# mipi.net
KiCad netlist of a schematic drawn in EasyEDA Pro
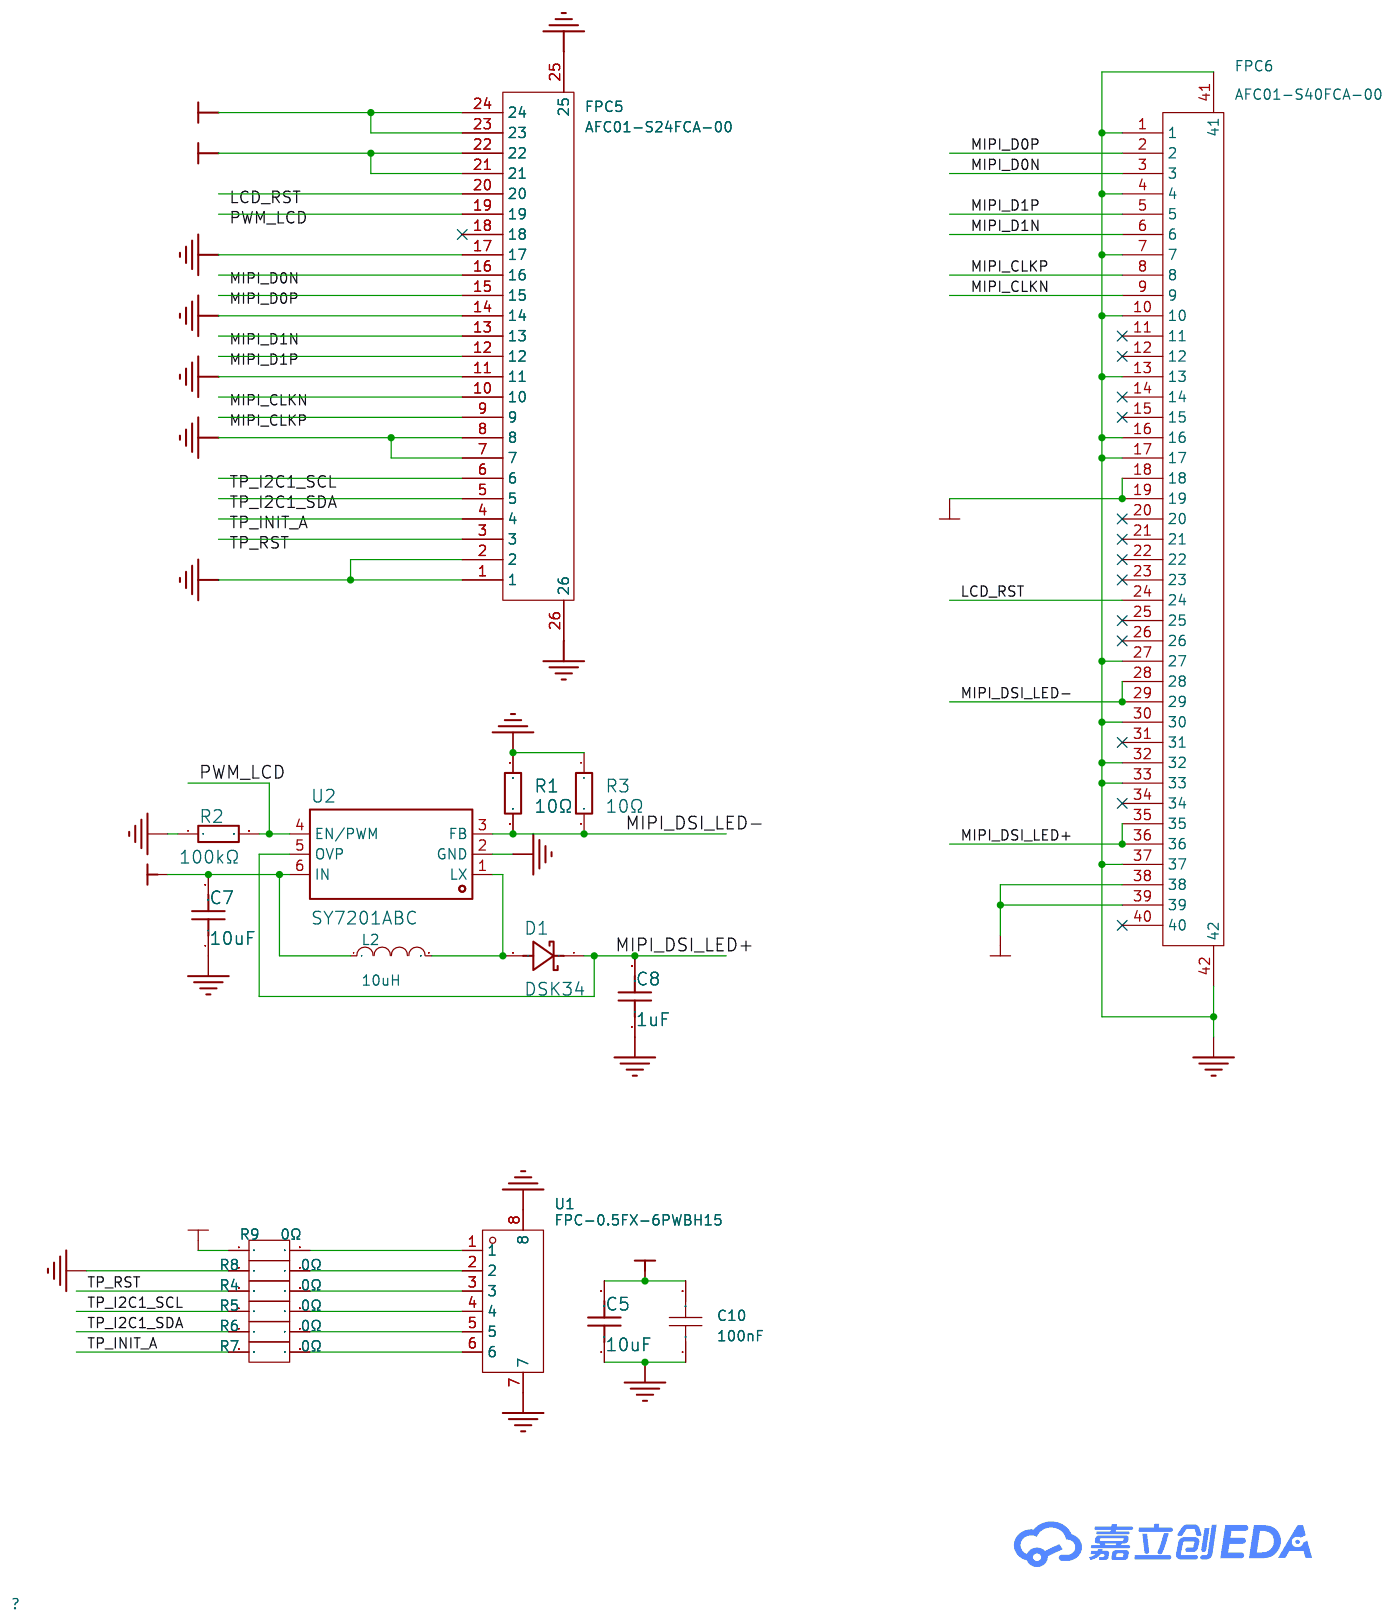
[diagram p0: schematic sheet]

(export (version "E")
  (design (tool "Eeschema 10.0.6"))
  (components
    (comp (ref "C5")
      (value "10uF")
      (fields
        (field (name "Manufacturer Part") "CL21A106KAYNNNE")
        (field (name "Manufacturer") "SAMSUNG(三星)")
      )
      (libsource (lib "easyedapro") (part "CapAcitance"))
    )
    (comp (ref "C7")
      (value "10uF")
      (fields
        (field (name "Manufacturer Part") "CL21A106KAYNNNE")
        (field (name "Manufacturer") "SAMSUNG(三星)")
      )
      (libsource (lib "easyedapro") (part "CapAcitance"))
    )
    (comp (ref "C8")
      (value "1uF")
      (description "容值:1uF;精度:±10%;额定电压:50V;温度系数:X7R;")
      (fields
        (field (name "Manufacturer Part") "CL21B105KBFNNNE")
        (field (name "Manufacturer") "SAMSUNG(三星)")
      )
      (libsource (lib "easyedapro") (part "CapAcitance"))
    )
    (comp (ref "C10")
      (value "100nF")
      (footprint "easyedapro:CAP-SMD_L2.0-W1.25")
      (description "容值:100nF;精度:±10%;额定电压:50V;温度系数:X7R;")
      (fields
        (field (name "Manufacturer Part") "C0805S104K5RACAUTO")
        (field (name "Manufacturer") "KEMET(基美)")
      )
      (libsource (lib "easyedapro") (part "FCC0805B104K500DT"))
    )
    (comp (ref "D1")
      (value "DSK34")
      (footprint "easyedapro:SOD-123_L2.8-W1.8-LS3.7-RD")
      (fields (field (name "Manufacturer") "FUXINSEMI(富芯森美)"))
      (libsource (lib "easyedapro") (part "DSK34_C908230"))
    )
    (comp (ref "FPC5")
      (value "AFC01-S24FCA-00")
      (footprint "easyedapro:FPC-SMD_24P-P0.50_AFC01-S24FCA-00")
      (description "锁定特性:翻盖式;触点类型:下接;触点数量:24P;间距:0.5mm;安装类型:卧贴;")
      (fields (field (name "Manufacturer") "JS(钜硕电子)"))
      (libsource (lib "easyedapro") (part "AFC01-S24FCA-00"))
    )
    (comp (ref "FPC6")
      (value "AFC01-S40FCA-00")
      (footprint "easyedapro:FPC-SMD_AFC01-S40FCA-00")
      (description "锁定特性:翻盖式;触点类型:下接;触点数量:40P;间距:0.5mm;安装方式:卧贴;工作温度:-45°C~+85°C;")
      (fields (field (name "Manufacturer") "JS(钜硕电子)"))
      (libsource (lib "easyedapro") (part "AFC01-S40FCA-00"))
    )
    (comp (ref "L2")
      (value "10uH")
      (footprint "easyedapro:IND-SMD_L7.3-W6.8")
      (description "电感值:10uH;精度:±20%;额定电流:4.5A;饱和电流(Isat):5.5A;类型:一体成型电感;")
      (fields (field (name "Manufacturer Part") "FXL0630-100-M") (field (name "Manufacturer") "cjiang(长江微电)"))
      (libsource (lib "easyedapro") (part "FXL0630-100-M"))
    )
    (comp (ref "R1")
      (value "10Ω")
      (fields
        (field (name "Manufacturer Part") "0603WAF360KT5E")
        (field (name "Manufacturer") "UNI-ROYAL(厚声)")
      )
      (libsource (lib "easyedapro") (part "电阻"))
    )
    (comp (ref "R2")
      (value "100kΩ")
      (fields
        (field (name "Manufacturer Part") "0805W8F1003T5E")
        (field (name "Manufacturer") "UNI-ROYAL(厚声)")
      )
      (libsource (lib "easyedapro") (part "电阻"))
    )
    (comp (ref "R3")
      (value "10Ω")
      (fields
        (field (name "Manufacturer Part") "0603WAF360KT5E")
        (field (name "Manufacturer") "UNI-ROYAL(厚声)")
      )
      (libsource (lib "easyedapro") (part "电阻"))
    )
    (comp (ref "R4")
      (value "0Ω")
      (footprint "easyedapro:R0805")
      (description "电阻类型:合金电阻;阻值:0Ω;精度:±1%;功率:500mW;温度系数:±50ppm/°C;安装方式:贴片;")
      (fields (field (name "Manufacturer Part") "RE0805FAR000") (field (name "Manufacturer") "JIERR(捷而瑞)"))
      (libsource (lib "easyedapro") (part "RE0805FAR000"))
    )
    (comp (ref "R5")
      (value "0Ω")
      (footprint "easyedapro:R0805")
      (description "电阻类型:合金电阻;阻值:0Ω;精度:±1%;功率:500mW;温度系数:±50ppm/°C;安装方式:贴片;")
      (fields (field (name "Manufacturer Part") "RE0805FAR000") (field (name "Manufacturer") "JIERR(捷而瑞)"))
      (libsource (lib "easyedapro") (part "RE0805FAR000"))
    )
    (comp (ref "R6")
      (value "0Ω")
      (footprint "easyedapro:R0805")
      (description "电阻类型:合金电阻;阻值:0Ω;精度:±1%;功率:500mW;温度系数:±50ppm/°C;安装方式:贴片;")
      (fields (field (name "Manufacturer Part") "RE0805FAR000") (field (name "Manufacturer") "JIERR(捷而瑞)"))
      (libsource (lib "easyedapro") (part "RE0805FAR000"))
    )
    (comp (ref "R7")
      (value "0Ω")
      (footprint "easyedapro:R0805")
      (description "电阻类型:合金电阻;阻值:0Ω;精度:±1%;功率:500mW;温度系数:±50ppm/°C;安装方式:贴片;")
      (fields (field (name "Manufacturer Part") "RE0805FAR000") (field (name "Manufacturer") "JIERR(捷而瑞)"))
      (libsource (lib "easyedapro") (part "RE0805FAR000"))
    )
    (comp (ref "R8")
      (value "0Ω")
      (footprint "easyedapro:R0805")
      (description "电阻类型:合金电阻;阻值:0Ω;精度:±1%;功率:500mW;温度系数:±50ppm/°C;安装方式:贴片;")
      (fields (field (name "Manufacturer Part") "RE0805FAR000") (field (name "Manufacturer") "JIERR(捷而瑞)"))
      (libsource (lib "easyedapro") (part "RE0805FAR000"))
    )
    (comp (ref "R9")
      (value "0Ω")
      (footprint "easyedapro:R0805")
      (description "电阻类型:合金电阻;阻值:0Ω;精度:±1%;功率:500mW;温度系数:±50ppm/°C;安装方式:贴片;")
      (fields (field (name "Manufacturer Part") "RE0805FAR000") (field (name "Manufacturer") "JIERR(捷而瑞)"))
      (libsource (lib "easyedapro") (part "RE0805FAR000"))
    )
    (comp (ref "U1")
      (value "FPC-0.5FX-6PWBH15")
      (footprint "easyedapro:FPC-SMD_XUNPU_FPC-0.5FX-6PWBH15")
      (fields (field (name "Manufacturer") "XUNPU(讯普)"))
      (libsource (lib "easyedapro") (part "FPC-0.5FX-6PWBH15"))
    )
    (comp (ref "U2")
      (value "SY7201ABC")
      (fields (field (name "Manufacturer") "Silergy(矽力杰)"))
      (libsource (lib "easyedapro") (part "SY7201ABC"))
    )
  )
  (nets
    (net (code "1") (name "/LCD_RST") (class "Default")
      (node (ref "FPC5") (pin "20") (pinfunction "20_20") (pintype "unspecified"))
      (node (ref "FPC6") (pin "24") (pinfunction "24_24") (pintype "unspecified"))
    )
    (net (code "2") (name "/MIPI_CLKN") (class "Default")
      (node (ref "FPC5") (pin "10") (pinfunction "10_10") (pintype "unspecified"))
      (node (ref "FPC6") (pin "9") (pinfunction "9_9") (pintype "unspecified"))
    )
    (net (code "3") (name "/MIPI_CLKP") (class "Default")
      (node (ref "FPC5") (pin "9") (pinfunction "9_9") (pintype "unspecified"))
      (node (ref "FPC6") (pin "8") (pinfunction "8_8") (pintype "unspecified"))
    )
    (net (code "4") (name "/MIPI_D0N") (class "Default")
      (node (ref "FPC5") (pin "16") (pinfunction "16_16") (pintype "unspecified"))
      (node (ref "FPC6") (pin "3") (pinfunction "3_3") (pintype "unspecified"))
    )
    (net (code "5") (name "/MIPI_D0P") (class "Default")
      (node (ref "FPC5") (pin "15") (pinfunction "15_15") (pintype "unspecified"))
      (node (ref "FPC6") (pin "2") (pinfunction "2_2") (pintype "unspecified"))
    )
    (net (code "6") (name "/MIPI_D1N") (class "Default")
      (node (ref "FPC5") (pin "13") (pinfunction "13_13") (pintype "unspecified"))
      (node (ref "FPC6") (pin "6") (pinfunction "6_6") (pintype "unspecified"))
    )
    (net (code "7") (name "/MIPI_D1P") (class "Default")
      (node (ref "FPC5") (pin "12") (pinfunction "12_12") (pintype "unspecified"))
      (node (ref "FPC6") (pin "5") (pinfunction "5_5") (pintype "unspecified"))
    )
    (net (code "8") (name "/MIPI_DSI_LED+") (class "Default")
      (node (ref "C8") (pin "2") (pinfunction "2_2") (pintype "input"))
      (node (ref "D1") (pin "1") (pinfunction "K_1") (pintype "unspecified"))
      (node (ref "FPC6") (pin "35") (pinfunction "35_35") (pintype "unspecified"))
      (node (ref "FPC6") (pin "36") (pinfunction "36_36") (pintype "unspecified"))
      (node (ref "U2") (pin "5") (pinfunction "OVP_5") (pintype "unspecified"))
    )
    (net (code "9") (name "/MIPI_DSI_LED-") (class "Default")
      (node (ref "FPC6") (pin "28") (pinfunction "28_28") (pintype "unspecified"))
      (node (ref "FPC6") (pin "29") (pinfunction "29_29") (pintype "unspecified"))
      (node (ref "R1") (pin "2") (pinfunction "2_2") (pintype "input"))
      (node (ref "R3") (pin "2") (pinfunction "2_2") (pintype "input"))
      (node (ref "U2") (pin "3") (pinfunction "FB_3") (pintype "unspecified"))
    )
    (net (code "10") (name "/PWM_LCD") (class "Default")
      (node (ref "FPC5") (pin "19") (pinfunction "19_19") (pintype "unspecified"))
      (node (ref "R2") (pin "2") (pinfunction "2_2") (pintype "input"))
      (node (ref "U2") (pin "4") (pinfunction "EN/PWM_4") (pintype "unspecified"))
    )
    (net (code "11") (name "/TP_I2C1_SCL") (class "Default")
      (node (ref "FPC5") (pin "6") (pinfunction "6_6") (pintype "unspecified"))
      (node (ref "R5") (pin "1") (pinfunction "1_1") (pintype "unspecified"))
    )
    (net (code "12") (name "/TP_I2C1_SDA") (class "Default")
      (node (ref "FPC5") (pin "5") (pinfunction "5_5") (pintype "unspecified"))
      (node (ref "R6") (pin "1") (pinfunction "1_1") (pintype "unspecified"))
    )
    (net (code "13") (name "/TP_INIT_A") (class "Default")
      (node (ref "FPC5") (pin "4") (pinfunction "4_4") (pintype "unspecified"))
      (node (ref "R7") (pin "1") (pinfunction "1_1") (pintype "unspecified"))
    )
    (net (code "14") (name "/TP_RST") (class "Default")
      (node (ref "FPC5") (pin "3") (pinfunction "3_3") (pintype "unspecified"))
      (node (ref "R4") (pin "1") (pinfunction "1_1") (pintype "unspecified"))
    )
    (net (code "15") (name "GND") (class "Default")
      (node (ref "C10") (pin "1") (pinfunction "1_1") (pintype "unspecified"))
      (node (ref "C5") (pin "1") (pinfunction "1_1") (pintype "input"))
      (node (ref "C7") (pin "1") (pinfunction "1_1") (pintype "input"))
      (node (ref "C8") (pin "1") (pinfunction "1_1") (pintype "input"))
      (node (ref "FPC5") (pin "1") (pinfunction "1_1") (pintype "unspecified"))
      (node (ref "FPC5") (pin "11") (pinfunction "11_11") (pintype "unspecified"))
      (node (ref "FPC5") (pin "14") (pinfunction "14_14") (pintype "unspecified"))
      (node (ref "FPC5") (pin "17") (pinfunction "17_17") (pintype "unspecified"))
      (node (ref "FPC5") (pin "2") (pinfunction "2_2") (pintype "unspecified"))
      (node (ref "FPC5") (pin "25") (pinfunction "25_25") (pintype "unspecified"))
      (node (ref "FPC5") (pin "26") (pinfunction "26_26") (pintype "unspecified"))
      (node (ref "FPC5") (pin "7") (pinfunction "7_7") (pintype "unspecified"))
      (node (ref "FPC5") (pin "8") (pinfunction "8_8") (pintype "unspecified"))
      (node (ref "FPC6") (pin "1") (pinfunction "1_1") (pintype "unspecified"))
      (node (ref "FPC6") (pin "10") (pinfunction "10_10") (pintype "unspecified"))
      (node (ref "FPC6") (pin "13") (pinfunction "13_13") (pintype "unspecified"))
      (node (ref "FPC6") (pin "16") (pinfunction "16_16") (pintype "unspecified"))
      (node (ref "FPC6") (pin "17") (pinfunction "17_17") (pintype "unspecified"))
      (node (ref "FPC6") (pin "27") (pinfunction "27_27") (pintype "unspecified"))
      (node (ref "FPC6") (pin "30") (pinfunction "30_30") (pintype "unspecified"))
      (node (ref "FPC6") (pin "32") (pinfunction "32_32") (pintype "unspecified"))
      (node (ref "FPC6") (pin "33") (pinfunction "33_33") (pintype "unspecified"))
      (node (ref "FPC6") (pin "37") (pinfunction "37_37") (pintype "unspecified"))
      (node (ref "FPC6") (pin "4") (pinfunction "4_4") (pintype "unspecified"))
      (node (ref "FPC6") (pin "41") (pinfunction "41_41") (pintype "unspecified"))
      (node (ref "FPC6") (pin "42") (pinfunction "42_42") (pintype "unspecified"))
      (node (ref "FPC6") (pin "7") (pinfunction "7_7") (pintype "unspecified"))
      (node (ref "R1") (pin "1") (pinfunction "1_1") (pintype "input"))
      (node (ref "R2") (pin "1") (pinfunction "1_1") (pintype "input"))
      (node (ref "R3") (pin "1") (pinfunction "1_1") (pintype "input"))
      (node (ref "R8") (pin "1") (pinfunction "1_1") (pintype "unspecified"))
      (node (ref "U1") (pin "7") (pinfunction "7_7") (pintype "unspecified"))
      (node (ref "U1") (pin "8") (pinfunction "8_8") (pintype "unspecified"))
      (node (ref "U2") (pin "2") (pinfunction "GND_2") (pintype "unspecified"))
    )
    (net (code "16") (name "Net-(D1-A)") (class "Default")
      (node (ref "D1") (pin "2") (pinfunction "A_2") (pintype "unspecified"))
      (node (ref "L2") (pin "2") (pinfunction "2_2") (pintype "unspecified"))
      (node (ref "U2") (pin "1") (pinfunction "LX_1") (pintype "unspecified"))
    )
    (net (code "17") (name "Net-(R4-Pad2)") (class "Default")
      (node (ref "R4") (pin "2") (pinfunction "2_2") (pintype "unspecified"))
      (node (ref "U1") (pin "3") (pinfunction "3_3") (pintype "unspecified"))
    )
    (net (code "18") (name "Net-(R5-Pad2)") (class "Default")
      (node (ref "R5") (pin "2") (pinfunction "2_2") (pintype "unspecified"))
      (node (ref "U1") (pin "4") (pinfunction "4_4") (pintype "unspecified"))
    )
    (net (code "19") (name "Net-(R6-Pad2)") (class "Default")
      (node (ref "R6") (pin "2") (pinfunction "2_2") (pintype "unspecified"))
      (node (ref "U1") (pin "5") (pinfunction "5_5") (pintype "unspecified"))
    )
    (net (code "20") (name "Net-(R7-Pad2)") (class "Default")
      (node (ref "R7") (pin "2") (pinfunction "2_2") (pintype "unspecified"))
      (node (ref "U1") (pin "6") (pinfunction "6_6") (pintype "unspecified"))
    )
    (net (code "21") (name "Net-(R8-Pad2)") (class "Default")
      (node (ref "R8") (pin "2") (pinfunction "2_2") (pintype "unspecified"))
      (node (ref "U1") (pin "2") (pinfunction "2_2") (pintype "unspecified"))
    )
    (net (code "22") (name "Net-(R9-Pad2)") (class "Default")
      (node (ref "R9") (pin "2") (pinfunction "2_2") (pintype "unspecified"))
      (node (ref "U1") (pin "1") (pinfunction "1_1") (pintype "unspecified"))
    )
    (net (code "23") (name "VCC_3V3") (class "Default")
      (node (ref "C10") (pin "2") (pinfunction "2_2") (pintype "unspecified"))
      (node (ref "C5") (pin "2") (pinfunction "2_2") (pintype "input"))
      (node (ref "C7") (pin "2") (pinfunction "2_2") (pintype "input"))
      (node (ref "FPC5") (pin "21") (pinfunction "21_21") (pintype "unspecified"))
      (node (ref "FPC5") (pin "22") (pinfunction "22_22") (pintype "unspecified"))
      (node (ref "FPC6") (pin "18") (pinfunction "18_18") (pintype "unspecified"))
      (node (ref "FPC6") (pin "19") (pinfunction "19_19") (pintype "unspecified"))
      (node (ref "FPC6") (pin "38") (pinfunction "38_38") (pintype "unspecified"))
      (node (ref "FPC6") (pin "39") (pinfunction "39_39") (pintype "unspecified"))
      (node (ref "L2") (pin "1") (pinfunction "1_1") (pintype "unspecified"))
      (node (ref "R9") (pin "1") (pinfunction "1_1") (pintype "unspecified"))
      (node (ref "U2") (pin "6") (pinfunction "IN_6") (pintype "unspecified"))
    )
    (net (code "24") (name "VCC_5V") (class "Default")
      (node (ref "FPC5") (pin "23") (pinfunction "23_23") (pintype "unspecified"))
      (node (ref "FPC5") (pin "24") (pinfunction "24_24") (pintype "unspecified"))
    )
    (net (code "25") (name "unconnected-(FPC5-Pad18)") (class "Default")
      (node (ref "FPC5") (pin "18") (pinfunction "18_18") (pintype "unspecified+no_connect"))
    )
    (net (code "26") (name "unconnected-(FPC6-Pad11)") (class "Default")
      (node (ref "FPC6") (pin "11") (pinfunction "11_11") (pintype "unspecified+no_connect"))
    )
    (net (code "27") (name "unconnected-(FPC6-Pad12)") (class "Default")
      (node (ref "FPC6") (pin "12") (pinfunction "12_12") (pintype "unspecified+no_connect"))
    )
    (net (code "28") (name "unconnected-(FPC6-Pad14)") (class "Default")
      (node (ref "FPC6") (pin "14") (pinfunction "14_14") (pintype "unspecified+no_connect"))
    )
    (net (code "29") (name "unconnected-(FPC6-Pad15)") (class "Default")
      (node (ref "FPC6") (pin "15") (pinfunction "15_15") (pintype "unspecified+no_connect"))
    )
    (net (code "30") (name "unconnected-(FPC6-Pad20)") (class "Default")
      (node (ref "FPC6") (pin "20") (pinfunction "20_20") (pintype "unspecified+no_connect"))
    )
    (net (code "31") (name "unconnected-(FPC6-Pad21)") (class "Default")
      (node (ref "FPC6") (pin "21") (pinfunction "21_21") (pintype "unspecified+no_connect"))
    )
    (net (code "32") (name "unconnected-(FPC6-Pad22)") (class "Default")
      (node (ref "FPC6") (pin "22") (pinfunction "22_22") (pintype "unspecified+no_connect"))
    )
    (net (code "33") (name "unconnected-(FPC6-Pad23)") (class "Default")
      (node (ref "FPC6") (pin "23") (pinfunction "23_23") (pintype "unspecified+no_connect"))
    )
    (net (code "34") (name "unconnected-(FPC6-Pad25)") (class "Default")
      (node (ref "FPC6") (pin "25") (pinfunction "25_25") (pintype "unspecified+no_connect"))
    )
    (net (code "35") (name "unconnected-(FPC6-Pad26)") (class "Default")
      (node (ref "FPC6") (pin "26") (pinfunction "26_26") (pintype "unspecified+no_connect"))
    )
    (net (code "36") (name "unconnected-(FPC6-Pad31)") (class "Default")
      (node (ref "FPC6") (pin "31") (pinfunction "31_31") (pintype "unspecified+no_connect"))
    )
    (net (code "37") (name "unconnected-(FPC6-Pad34)") (class "Default")
      (node (ref "FPC6") (pin "34") (pinfunction "34_34") (pintype "unspecified+no_connect"))
    )
    (net (code "38") (name "unconnected-(FPC6-Pad40)") (class "Default")
      (node (ref "FPC6") (pin "40") (pinfunction "40_40") (pintype "unspecified+no_connect"))
    )
  )
)
